# TLC5955.net
KiCad netlist of a schematic drawn in Altium Designer
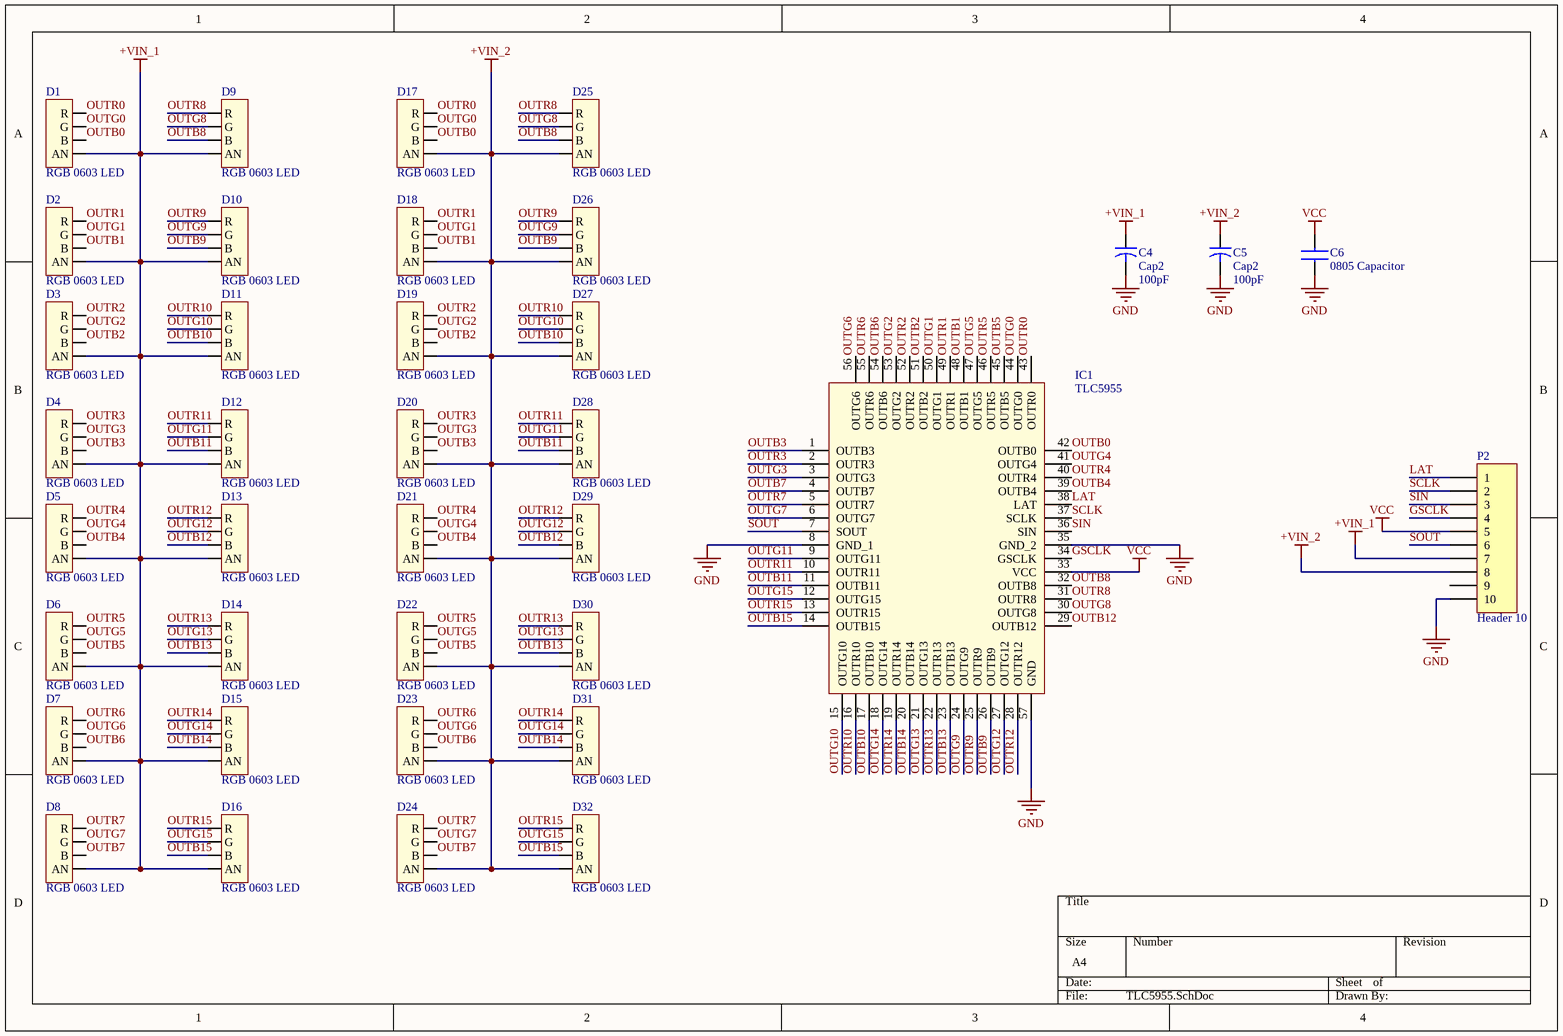
[diagram p0: TLC5955.SchDoc]

(export (version "E")
  (design (tool "Eeschema 10.0.6"))
  (components
    (comp (ref "C4")
      (value "Cap2")
      (footprint "CAPR5-4X5")
      (description "Capacitor")
      (fields (field (name "ALTIUM_VALUE") "100pF") (field (name "PUBLISHER") "Altium Limited"))
      (libsource (lib "Miscellaneous Devices") (part "Cap2"))
    )
    (comp (ref "C5")
      (value "Cap2")
      (footprint "CAPR5-4X5")
      (description "Capacitor")
      (fields (field (name "ALTIUM_VALUE") "100pF") (field (name "PUBLISHER") "Altium Limited"))
      (libsource (lib "Miscellaneous Devices") (part "Cap2"))
    )
    (comp (ref "C6")
      (value "0805 Capacitor")
      (footprint "0805 Capacitor")
      (libsource (lib "Schlib1") (part "0805 Capacitor"))
    )
    (comp (ref "D1")
      (value "RGB 0603 LED")
      (footprint "RGB LED")
      (libsource (lib "") (part "RGB 0603 LED_1"))
    )
    (comp (ref "D2")
      (value "RGB 0603 LED")
      (footprint "RGB LED")
      (libsource (lib "") (part "RGB 0603 LED_1"))
    )
    (comp (ref "D3")
      (value "RGB 0603 LED")
      (footprint "RGB LED")
      (libsource (lib "") (part "RGB 0603 LED_1"))
    )
    (comp (ref "D4")
      (value "RGB 0603 LED")
      (footprint "RGB LED")
      (libsource (lib "") (part "RGB 0603 LED_1"))
    )
    (comp (ref "D5")
      (value "RGB 0603 LED")
      (footprint "RGB LED")
      (libsource (lib "") (part "RGB 0603 LED_1"))
    )
    (comp (ref "D6")
      (value "RGB 0603 LED")
      (footprint "RGB LED")
      (libsource (lib "") (part "RGB 0603 LED_1"))
    )
    (comp (ref "D7")
      (value "RGB 0603 LED")
      (footprint "RGB LED")
      (libsource (lib "") (part "RGB 0603 LED_1"))
    )
    (comp (ref "D8")
      (value "RGB 0603 LED")
      (footprint "RGB LED")
      (libsource (lib "") (part "RGB 0603 LED_1"))
    )
    (comp (ref "D9")
      (value "RGB 0603 LED")
      (footprint "RGB LED")
      (libsource (lib "Schlib1") (part "RGB 0603 LED"))
    )
    (comp (ref "D10")
      (value "RGB 0603 LED")
      (footprint "RGB LED")
      (libsource (lib "Schlib1") (part "RGB 0603 LED"))
    )
    (comp (ref "D11")
      (value "RGB 0603 LED")
      (footprint "RGB LED")
      (libsource (lib "Schlib1") (part "RGB 0603 LED"))
    )
    (comp (ref "D12")
      (value "RGB 0603 LED")
      (footprint "RGB LED")
      (libsource (lib "Schlib1") (part "RGB 0603 LED"))
    )
    (comp (ref "D13")
      (value "RGB 0603 LED")
      (footprint "RGB LED")
      (libsource (lib "Schlib1") (part "RGB 0603 LED"))
    )
    (comp (ref "D14")
      (value "RGB 0603 LED")
      (footprint "RGB LED")
      (libsource (lib "Schlib1") (part "RGB 0603 LED"))
    )
    (comp (ref "D15")
      (value "RGB 0603 LED")
      (footprint "RGB LED")
      (libsource (lib "Schlib1") (part "RGB 0603 LED"))
    )
    (comp (ref "D16")
      (value "RGB 0603 LED")
      (footprint "RGB LED")
      (libsource (lib "Schlib1") (part "RGB 0603 LED"))
    )
    (comp (ref "D17")
      (value "RGB 0603 LED")
      (footprint "RGB LED")
      (libsource (lib "") (part "RGB 0603 LED_1"))
    )
    (comp (ref "D18")
      (value "RGB 0603 LED")
      (footprint "RGB LED")
      (libsource (lib "") (part "RGB 0603 LED_1"))
    )
    (comp (ref "D19")
      (value "RGB 0603 LED")
      (footprint "RGB LED")
      (libsource (lib "") (part "RGB 0603 LED_1"))
    )
    (comp (ref "D20")
      (value "RGB 0603 LED")
      (footprint "RGB LED")
      (libsource (lib "") (part "RGB 0603 LED_1"))
    )
    (comp (ref "D21")
      (value "RGB 0603 LED")
      (footprint "RGB LED")
      (libsource (lib "") (part "RGB 0603 LED_1"))
    )
    (comp (ref "D22")
      (value "RGB 0603 LED")
      (footprint "RGB LED")
      (libsource (lib "") (part "RGB 0603 LED_1"))
    )
    (comp (ref "D23")
      (value "RGB 0603 LED")
      (footprint "RGB LED")
      (libsource (lib "") (part "RGB 0603 LED_1"))
    )
    (comp (ref "D24")
      (value "RGB 0603 LED")
      (footprint "RGB LED")
      (libsource (lib "") (part "RGB 0603 LED_1"))
    )
    (comp (ref "D25")
      (value "RGB 0603 LED")
      (footprint "RGB LED")
      (libsource (lib "Schlib1") (part "RGB 0603 LED"))
    )
    (comp (ref "D26")
      (value "RGB 0603 LED")
      (footprint "RGB LED")
      (libsource (lib "Schlib1") (part "RGB 0603 LED"))
    )
    (comp (ref "D27")
      (value "RGB 0603 LED")
      (footprint "RGB LED")
      (libsource (lib "Schlib1") (part "RGB 0603 LED"))
    )
    (comp (ref "D28")
      (value "RGB 0603 LED")
      (footprint "RGB LED")
      (libsource (lib "Schlib1") (part "RGB 0603 LED"))
    )
    (comp (ref "D29")
      (value "RGB 0603 LED")
      (footprint "RGB LED")
      (libsource (lib "Schlib1") (part "RGB 0603 LED"))
    )
    (comp (ref "D30")
      (value "RGB 0603 LED")
      (footprint "RGB LED")
      (libsource (lib "Schlib1") (part "RGB 0603 LED"))
    )
    (comp (ref "D31")
      (value "RGB 0603 LED")
      (footprint "RGB LED")
      (libsource (lib "Schlib1") (part "RGB 0603 LED"))
    )
    (comp (ref "D32")
      (value "RGB 0603 LED")
      (footprint "RGB LED")
      (libsource (lib "Schlib1") (part "RGB 0603 LED"))
    )
    (comp (ref "IC1") (value "TLC5955") (footprint "TLC5955") (libsource (lib "Schlib1") (part "TLC5955")))
    (comp (ref "P2")
      (value "Header 10")
      (footprint "HDR1X10")
      (description "Header, 10-Pin")
      (fields (field (name "PUBLISHER") "Altium Limited"))
      (libsource (lib "Miscellaneous Connectors") (part "Header 10"))
    )
  )
  (nets
    (net (code "1") (name "+VIN_1") (class "Default")
      (node (ref "C4") (pin "1") (pinfunction "1_1") (pintype "passive"))
      (node (ref "D1") (pin "4") (pinfunction "AN_4") (pintype "passive"))
      (node (ref "D10") (pin "4") (pinfunction "AN_4") (pintype "passive"))
      (node (ref "D11") (pin "4") (pinfunction "AN_4") (pintype "passive"))
      (node (ref "D12") (pin "4") (pinfunction "AN_4") (pintype "passive"))
      (node (ref "D13") (pin "4") (pinfunction "AN_4") (pintype "passive"))
      (node (ref "D14") (pin "4") (pinfunction "AN_4") (pintype "passive"))
      (node (ref "D15") (pin "4") (pinfunction "AN_4") (pintype "passive"))
      (node (ref "D16") (pin "4") (pinfunction "AN_4") (pintype "passive"))
      (node (ref "D2") (pin "4") (pinfunction "AN_4") (pintype "passive"))
      (node (ref "D3") (pin "4") (pinfunction "AN_4") (pintype "passive"))
      (node (ref "D4") (pin "4") (pinfunction "AN_4") (pintype "passive"))
      (node (ref "D5") (pin "4") (pinfunction "AN_4") (pintype "passive"))
      (node (ref "D6") (pin "4") (pinfunction "AN_4") (pintype "passive"))
      (node (ref "D7") (pin "4") (pinfunction "AN_4") (pintype "passive"))
      (node (ref "D8") (pin "4") (pinfunction "AN_4") (pintype "passive"))
      (node (ref "D9") (pin "4") (pinfunction "AN_4") (pintype "passive"))
      (node (ref "P2") (pin "7") (pinfunction "7_7") (pintype "passive"))
    )
    (net (code "2") (name "+VIN_2") (class "Default")
      (node (ref "C5") (pin "1") (pinfunction "1_1") (pintype "passive"))
      (node (ref "D17") (pin "4") (pinfunction "AN_4") (pintype "passive"))
      (node (ref "D18") (pin "4") (pinfunction "AN_4") (pintype "passive"))
      (node (ref "D19") (pin "4") (pinfunction "AN_4") (pintype "passive"))
      (node (ref "D20") (pin "4") (pinfunction "AN_4") (pintype "passive"))
      (node (ref "D21") (pin "4") (pinfunction "AN_4") (pintype "passive"))
      (node (ref "D22") (pin "4") (pinfunction "AN_4") (pintype "passive"))
      (node (ref "D23") (pin "4") (pinfunction "AN_4") (pintype "passive"))
      (node (ref "D24") (pin "4") (pinfunction "AN_4") (pintype "passive"))
      (node (ref "D25") (pin "4") (pinfunction "AN_4") (pintype "passive"))
      (node (ref "D26") (pin "4") (pinfunction "AN_4") (pintype "passive"))
      (node (ref "D27") (pin "4") (pinfunction "AN_4") (pintype "passive"))
      (node (ref "D28") (pin "4") (pinfunction "AN_4") (pintype "passive"))
      (node (ref "D29") (pin "4") (pinfunction "AN_4") (pintype "passive"))
      (node (ref "D30") (pin "4") (pinfunction "AN_4") (pintype "passive"))
      (node (ref "D31") (pin "4") (pinfunction "AN_4") (pintype "passive"))
      (node (ref "D32") (pin "4") (pinfunction "AN_4") (pintype "passive"))
      (node (ref "P2") (pin "8") (pinfunction "8_8") (pintype "passive"))
    )
    (net (code "3") (name "/GSCLK") (class "Default")
      (node (ref "IC1") (pin "34") (pinfunction "GSCLK_34") (pintype "passive"))
      (node (ref "P2") (pin "4") (pinfunction "4_4") (pintype "passive"))
    )
    (net (code "4") (name "/LAT") (class "Default")
      (node (ref "IC1") (pin "38") (pinfunction "LAT_38") (pintype "passive"))
      (node (ref "P2") (pin "1") (pinfunction "1_1") (pintype "passive"))
    )
    (net (code "5") (name "/OUTB0") (class "Default")
      (node (ref "D1") (pin "3") (pinfunction "B_3") (pintype "passive"))
      (node (ref "D17") (pin "3") (pinfunction "B_3") (pintype "passive"))
      (node (ref "IC1") (pin "42") (pinfunction "OUTB0_42") (pintype "passive"))
    )
    (net (code "6") (name "/OUTB1") (class "Default")
      (node (ref "D18") (pin "3") (pinfunction "B_3") (pintype "passive"))
      (node (ref "D2") (pin "3") (pinfunction "B_3") (pintype "passive"))
      (node (ref "IC1") (pin "48") (pinfunction "OUTB1_48") (pintype "passive"))
    )
    (net (code "7") (name "/OUTB2") (class "Default")
      (node (ref "D19") (pin "3") (pinfunction "B_3") (pintype "passive"))
      (node (ref "D3") (pin "3") (pinfunction "B_3") (pintype "passive"))
      (node (ref "IC1") (pin "51") (pinfunction "OUTB2_51") (pintype "passive"))
    )
    (net (code "8") (name "/OUTB3") (class "Default")
      (node (ref "D20") (pin "3") (pinfunction "B_3") (pintype "passive"))
      (node (ref "D4") (pin "3") (pinfunction "B_3") (pintype "passive"))
      (node (ref "IC1") (pin "1") (pinfunction "OUTB3_1") (pintype "passive"))
    )
    (net (code "9") (name "/OUTB4") (class "Default")
      (node (ref "D21") (pin "3") (pinfunction "B_3") (pintype "passive"))
      (node (ref "D5") (pin "3") (pinfunction "B_3") (pintype "passive"))
      (node (ref "IC1") (pin "39") (pinfunction "OUTB4_39") (pintype "passive"))
    )
    (net (code "10") (name "/OUTB5") (class "Default")
      (node (ref "D22") (pin "3") (pinfunction "B_3") (pintype "passive"))
      (node (ref "D6") (pin "3") (pinfunction "B_3") (pintype "passive"))
      (node (ref "IC1") (pin "45") (pinfunction "OUTB5_45") (pintype "passive"))
    )
    (net (code "11") (name "/OUTB6") (class "Default")
      (node (ref "D23") (pin "3") (pinfunction "B_3") (pintype "passive"))
      (node (ref "D7") (pin "3") (pinfunction "B_3") (pintype "passive"))
      (node (ref "IC1") (pin "54") (pinfunction "OUTB6_54") (pintype "passive"))
    )
    (net (code "12") (name "/OUTB7") (class "Default")
      (node (ref "D24") (pin "3") (pinfunction "B_3") (pintype "passive"))
      (node (ref "D8") (pin "3") (pinfunction "B_3") (pintype "passive"))
      (node (ref "IC1") (pin "4") (pinfunction "OUTB7_4") (pintype "passive"))
    )
    (net (code "13") (name "/OUTB8") (class "Default")
      (node (ref "D25") (pin "3") (pinfunction "B_3") (pintype "passive"))
      (node (ref "D9") (pin "3") (pinfunction "B_3") (pintype "passive"))
      (node (ref "IC1") (pin "32") (pinfunction "OUTB8_32") (pintype "passive"))
    )
    (net (code "14") (name "/OUTB9") (class "Default")
      (node (ref "D10") (pin "3") (pinfunction "B_3") (pintype "passive"))
      (node (ref "D26") (pin "3") (pinfunction "B_3") (pintype "passive"))
      (node (ref "IC1") (pin "26") (pinfunction "OUTB9_26") (pintype "passive"))
    )
    (net (code "15") (name "/OUTB10") (class "Default")
      (node (ref "D11") (pin "3") (pinfunction "B_3") (pintype "passive"))
      (node (ref "D27") (pin "3") (pinfunction "B_3") (pintype "passive"))
      (node (ref "IC1") (pin "17") (pinfunction "OUTB10_17") (pintype "passive"))
    )
    (net (code "16") (name "/OUTB11") (class "Default")
      (node (ref "D12") (pin "3") (pinfunction "B_3") (pintype "passive"))
      (node (ref "D28") (pin "3") (pinfunction "B_3") (pintype "passive"))
      (node (ref "IC1") (pin "11") (pinfunction "OUTB11_11") (pintype "passive"))
    )
    (net (code "17") (name "/OUTB12") (class "Default")
      (node (ref "D13") (pin "3") (pinfunction "B_3") (pintype "passive"))
      (node (ref "D29") (pin "3") (pinfunction "B_3") (pintype "passive"))
      (node (ref "IC1") (pin "29") (pinfunction "OUTB12_29") (pintype "passive"))
    )
    (net (code "18") (name "/OUTB13") (class "Default")
      (node (ref "D14") (pin "3") (pinfunction "B_3") (pintype "passive"))
      (node (ref "D30") (pin "3") (pinfunction "B_3") (pintype "passive"))
      (node (ref "IC1") (pin "23") (pinfunction "OUTB13_23") (pintype "passive"))
    )
    (net (code "19") (name "/OUTB14") (class "Default")
      (node (ref "D15") (pin "3") (pinfunction "B_3") (pintype "passive"))
      (node (ref "D31") (pin "3") (pinfunction "B_3") (pintype "passive"))
      (node (ref "IC1") (pin "20") (pinfunction "OUTB14_20") (pintype "passive"))
    )
    (net (code "20") (name "/OUTB15") (class "Default")
      (node (ref "D16") (pin "3") (pinfunction "B_3") (pintype "passive"))
      (node (ref "D32") (pin "3") (pinfunction "B_3") (pintype "passive"))
      (node (ref "IC1") (pin "14") (pinfunction "OUTB15_14") (pintype "passive"))
    )
    (net (code "21") (name "/OUTG0") (class "Default")
      (node (ref "D1") (pin "2") (pinfunction "G_2") (pintype "passive"))
      (node (ref "D17") (pin "2") (pinfunction "G_2") (pintype "passive"))
      (node (ref "IC1") (pin "44") (pinfunction "OUTG0_44") (pintype "passive"))
    )
    (net (code "22") (name "/OUTG1") (class "Default")
      (node (ref "D18") (pin "2") (pinfunction "G_2") (pintype "passive"))
      (node (ref "D2") (pin "2") (pinfunction "G_2") (pintype "passive"))
      (node (ref "IC1") (pin "50") (pinfunction "OUTG1_50") (pintype "passive"))
    )
    (net (code "23") (name "/OUTG2") (class "Default")
      (node (ref "D19") (pin "2") (pinfunction "G_2") (pintype "passive"))
      (node (ref "D3") (pin "2") (pinfunction "G_2") (pintype "passive"))
      (node (ref "IC1") (pin "53") (pinfunction "OUTG2_53") (pintype "passive"))
    )
    (net (code "24") (name "/OUTG3") (class "Default")
      (node (ref "D20") (pin "2") (pinfunction "G_2") (pintype "passive"))
      (node (ref "D4") (pin "2") (pinfunction "G_2") (pintype "passive"))
      (node (ref "IC1") (pin "3") (pinfunction "OUTG3_3") (pintype "passive"))
    )
    (net (code "25") (name "/OUTG4") (class "Default")
      (node (ref "D21") (pin "2") (pinfunction "G_2") (pintype "passive"))
      (node (ref "D5") (pin "2") (pinfunction "G_2") (pintype "passive"))
      (node (ref "IC1") (pin "41") (pinfunction "OUTG4_41") (pintype "passive"))
    )
    (net (code "26") (name "/OUTG5") (class "Default")
      (node (ref "D22") (pin "2") (pinfunction "G_2") (pintype "passive"))
      (node (ref "D6") (pin "2") (pinfunction "G_2") (pintype "passive"))
      (node (ref "IC1") (pin "47") (pinfunction "OUTG5_47") (pintype "passive"))
    )
    (net (code "27") (name "/OUTG6") (class "Default")
      (node (ref "D23") (pin "2") (pinfunction "G_2") (pintype "passive"))
      (node (ref "D7") (pin "2") (pinfunction "G_2") (pintype "passive"))
      (node (ref "IC1") (pin "56") (pinfunction "OUTG6_56") (pintype "passive"))
    )
    (net (code "28") (name "/OUTG7") (class "Default")
      (node (ref "D24") (pin "2") (pinfunction "G_2") (pintype "passive"))
      (node (ref "D8") (pin "2") (pinfunction "G_2") (pintype "passive"))
      (node (ref "IC1") (pin "6") (pinfunction "OUTG7_6") (pintype "passive"))
    )
    (net (code "29") (name "/OUTG8") (class "Default")
      (node (ref "D25") (pin "2") (pinfunction "G_2") (pintype "passive"))
      (node (ref "D9") (pin "2") (pinfunction "G_2") (pintype "passive"))
      (node (ref "IC1") (pin "30") (pinfunction "OUTG8_30") (pintype "passive"))
    )
    (net (code "30") (name "/OUTG9") (class "Default")
      (node (ref "D10") (pin "2") (pinfunction "G_2") (pintype "passive"))
      (node (ref "D26") (pin "2") (pinfunction "G_2") (pintype "passive"))
      (node (ref "IC1") (pin "24") (pinfunction "OUTG9_24") (pintype "passive"))
    )
    (net (code "31") (name "/OUTG10") (class "Default")
      (node (ref "D11") (pin "2") (pinfunction "G_2") (pintype "passive"))
      (node (ref "D27") (pin "2") (pinfunction "G_2") (pintype "passive"))
      (node (ref "IC1") (pin "15") (pinfunction "OUTG10_15") (pintype "passive"))
    )
    (net (code "32") (name "/OUTG11") (class "Default")
      (node (ref "D12") (pin "2") (pinfunction "G_2") (pintype "passive"))
      (node (ref "D28") (pin "2") (pinfunction "G_2") (pintype "passive"))
      (node (ref "IC1") (pin "9") (pinfunction "OUTG11_9") (pintype "passive"))
    )
    (net (code "33") (name "/OUTG12") (class "Default")
      (node (ref "D13") (pin "2") (pinfunction "G_2") (pintype "passive"))
      (node (ref "D29") (pin "2") (pinfunction "G_2") (pintype "passive"))
      (node (ref "IC1") (pin "27") (pinfunction "OUTG12_27") (pintype "passive"))
    )
    (net (code "34") (name "/OUTG13") (class "Default")
      (node (ref "D14") (pin "2") (pinfunction "G_2") (pintype "passive"))
      (node (ref "D30") (pin "2") (pinfunction "G_2") (pintype "passive"))
      (node (ref "IC1") (pin "21") (pinfunction "OUTG13_21") (pintype "passive"))
    )
    (net (code "35") (name "/OUTG14") (class "Default")
      (node (ref "D15") (pin "2") (pinfunction "G_2") (pintype "passive"))
      (node (ref "D31") (pin "2") (pinfunction "G_2") (pintype "passive"))
      (node (ref "IC1") (pin "18") (pinfunction "OUTG14_18") (pintype "passive"))
    )
    (net (code "36") (name "/OUTG15") (class "Default")
      (node (ref "D16") (pin "2") (pinfunction "G_2") (pintype "passive"))
      (node (ref "D32") (pin "2") (pinfunction "G_2") (pintype "passive"))
      (node (ref "IC1") (pin "12") (pinfunction "OUTG15_12") (pintype "passive"))
    )
    (net (code "37") (name "/OUTR0") (class "Default")
      (node (ref "D1") (pin "1") (pinfunction "R_1") (pintype "passive"))
      (node (ref "D17") (pin "1") (pinfunction "R_1") (pintype "passive"))
      (node (ref "IC1") (pin "43") (pinfunction "OUTR0_43") (pintype "passive"))
    )
    (net (code "38") (name "/OUTR1") (class "Default")
      (node (ref "D18") (pin "1") (pinfunction "R_1") (pintype "passive"))
      (node (ref "D2") (pin "1") (pinfunction "R_1") (pintype "passive"))
      (node (ref "IC1") (pin "49") (pinfunction "OUTR1_49") (pintype "passive"))
    )
    (net (code "39") (name "/OUTR2") (class "Default")
      (node (ref "D19") (pin "1") (pinfunction "R_1") (pintype "passive"))
      (node (ref "D3") (pin "1") (pinfunction "R_1") (pintype "passive"))
      (node (ref "IC1") (pin "52") (pinfunction "OUTR2_52") (pintype "passive"))
    )
    (net (code "40") (name "/OUTR3") (class "Default")
      (node (ref "D20") (pin "1") (pinfunction "R_1") (pintype "passive"))
      (node (ref "D4") (pin "1") (pinfunction "R_1") (pintype "passive"))
      (node (ref "IC1") (pin "2") (pinfunction "OUTR3_2") (pintype "passive"))
    )
    (net (code "41") (name "/OUTR4") (class "Default")
      (node (ref "D21") (pin "1") (pinfunction "R_1") (pintype "passive"))
      (node (ref "D5") (pin "1") (pinfunction "R_1") (pintype "passive"))
      (node (ref "IC1") (pin "40") (pinfunction "OUTR4_40") (pintype "passive"))
    )
    (net (code "42") (name "/OUTR5") (class "Default")
      (node (ref "D22") (pin "1") (pinfunction "R_1") (pintype "passive"))
      (node (ref "D6") (pin "1") (pinfunction "R_1") (pintype "passive"))
      (node (ref "IC1") (pin "46") (pinfunction "OUTR5_46") (pintype "passive"))
    )
    (net (code "43") (name "/OUTR6") (class "Default")
      (node (ref "D23") (pin "1") (pinfunction "R_1") (pintype "passive"))
      (node (ref "D7") (pin "1") (pinfunction "R_1") (pintype "passive"))
      (node (ref "IC1") (pin "55") (pinfunction "OUTR6_55") (pintype "passive"))
    )
    (net (code "44") (name "/OUTR7") (class "Default")
      (node (ref "D24") (pin "1") (pinfunction "R_1") (pintype "passive"))
      (node (ref "D8") (pin "1") (pinfunction "R_1") (pintype "passive"))
      (node (ref "IC1") (pin "5") (pinfunction "OUTR7_5") (pintype "passive"))
    )
    (net (code "45") (name "/OUTR8") (class "Default")
      (node (ref "D25") (pin "1") (pinfunction "R_1") (pintype "passive"))
      (node (ref "D9") (pin "1") (pinfunction "R_1") (pintype "passive"))
      (node (ref "IC1") (pin "31") (pinfunction "OUTR8_31") (pintype "passive"))
    )
    (net (code "46") (name "/OUTR9") (class "Default")
      (node (ref "D10") (pin "1") (pinfunction "R_1") (pintype "passive"))
      (node (ref "D26") (pin "1") (pinfunction "R_1") (pintype "passive"))
      (node (ref "IC1") (pin "25") (pinfunction "OUTR9_25") (pintype "passive"))
    )
    (net (code "47") (name "/OUTR10") (class "Default")
      (node (ref "D11") (pin "1") (pinfunction "R_1") (pintype "passive"))
      (node (ref "D27") (pin "1") (pinfunction "R_1") (pintype "passive"))
      (node (ref "IC1") (pin "16") (pinfunction "OUTR10_16") (pintype "passive"))
    )
    (net (code "48") (name "/OUTR11") (class "Default")
      (node (ref "D12") (pin "1") (pinfunction "R_1") (pintype "passive"))
      (node (ref "D28") (pin "1") (pinfunction "R_1") (pintype "passive"))
      (node (ref "IC1") (pin "10") (pinfunction "OUTR11_10") (pintype "passive"))
    )
    (net (code "49") (name "/OUTR12") (class "Default")
      (node (ref "D13") (pin "1") (pinfunction "R_1") (pintype "passive"))
      (node (ref "D29") (pin "1") (pinfunction "R_1") (pintype "passive"))
      (node (ref "IC1") (pin "28") (pinfunction "OUTR12_28") (pintype "passive"))
    )
    (net (code "50") (name "/OUTR13") (class "Default")
      (node (ref "D14") (pin "1") (pinfunction "R_1") (pintype "passive"))
      (node (ref "D30") (pin "1") (pinfunction "R_1") (pintype "passive"))
      (node (ref "IC1") (pin "22") (pinfunction "OUTR13_22") (pintype "passive"))
    )
    (net (code "51") (name "/OUTR14") (class "Default")
      (node (ref "D15") (pin "1") (pinfunction "R_1") (pintype "passive"))
      (node (ref "D31") (pin "1") (pinfunction "R_1") (pintype "passive"))
      (node (ref "IC1") (pin "19") (pinfunction "OUTR14_19") (pintype "passive"))
    )
    (net (code "52") (name "/OUTR15") (class "Default")
      (node (ref "D16") (pin "1") (pinfunction "R_1") (pintype "passive"))
      (node (ref "D32") (pin "1") (pinfunction "R_1") (pintype "passive"))
      (node (ref "IC1") (pin "13") (pinfunction "OUTR15_13") (pintype "passive"))
    )
    (net (code "53") (name "/SCLK") (class "Default")
      (node (ref "IC1") (pin "37") (pinfunction "SCLK_37") (pintype "passive"))
      (node (ref "P2") (pin "2") (pinfunction "2_2") (pintype "passive"))
    )
    (net (code "54") (name "/SIN") (class "Default")
      (node (ref "IC1") (pin "36") (pinfunction "SIN_36") (pintype "passive"))
      (node (ref "P2") (pin "3") (pinfunction "3_3") (pintype "passive"))
    )
    (net (code "55") (name "/SOUT") (class "Default")
      (node (ref "IC1") (pin "7") (pinfunction "SOUT_7") (pintype "passive"))
      (node (ref "P2") (pin "6") (pinfunction "6_6") (pintype "passive"))
    )
    (net (code "56") (name "GND") (class "Default")
      (node (ref "C4") (pin "2") (pinfunction "2_2") (pintype "passive"))
      (node (ref "C5") (pin "2") (pinfunction "2_2") (pintype "passive"))
      (node (ref "C6") (pin "1") (pinfunction "1_1") (pintype "passive"))
      (node (ref "IC1") (pin "35") (pinfunction "GND_2_35") (pintype "passive"))
      (node (ref "IC1") (pin "57") (pinfunction "GND_57") (pintype "passive"))
      (node (ref "IC1") (pin "8") (pinfunction "GND_1_8") (pintype "passive"))
      (node (ref "P2") (pin "10") (pinfunction "10_10") (pintype "passive"))
    )
    (net (code "57") (name "VCC") (class "Default")
      (node (ref "C6") (pin "2") (pinfunction "2_2") (pintype "passive"))
      (node (ref "IC1") (pin "33") (pinfunction "VCC_33") (pintype "passive"))
      (node (ref "P2") (pin "5") (pinfunction "5_5") (pintype "passive"))
    )
    (net (code "58") (name "unconnected-(P2-Pad9)") (class "Default")
      (node (ref "P2") (pin "9") (pinfunction "9_9") (pintype "passive"))
    )
  )
)
